# BTB_CONN.net
KiCad netlist of a schematic drawn in Altium Designer
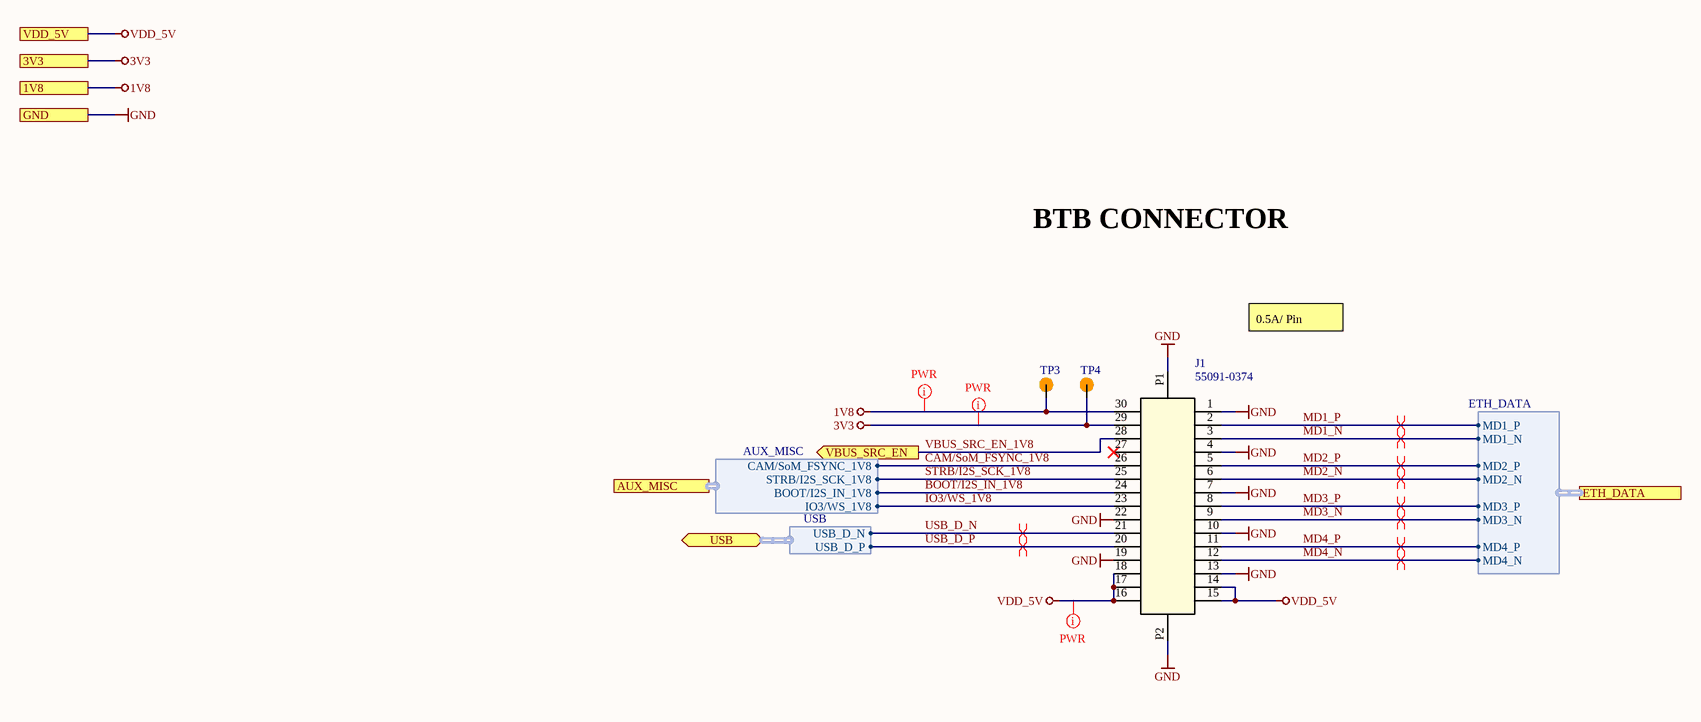
[diagram p0: BTB_CONN.SchDoc]

(export (version "E")
  (design (tool "Eeschema 10.0.6"))
  (components
    (comp (ref "J1")
      (value "55091-0374")
      (footprint "CON_550910374")
      (libsource (lib "Luxonis LLC") (part "55091-0374-Symbol-1"))
    )
    (comp (ref "TP3")
      (value "TP100_200_NS")
      (footprint "TP075_150_NS")
      (libsource (lib "Luxonis LLC") (part "TEST_POINT"))
    )
    (comp (ref "TP4")
      (value "TP100_200_NS")
      (footprint "TP075_150_NS")
      (libsource (lib "Luxonis LLC") (part "TEST_POINT"))
    )
  )
  (nets
    (net (code "4") (name "/BOOT{slash}I2S_IN_1V8") (class "Default")
      (node (ref "J1") (pin "24") (pinfunction "24_24") (pintype "passive"))
    )
    (net (code "5") (name "/CAM{slash}SoM_FSYNC_1V8") (class "Default")
      (node (ref "J1") (pin "26") (pinfunction "26_26") (pintype "passive"))
    )
    (net (code "6") (name "/IO3{slash}WS_1V8") (class "Default")
      (node (ref "J1") (pin "23") (pinfunction "23_23") (pintype "passive"))
    )
    (net (code "7") (name "/MD1_N") (class "Default")
      (node (ref "J1") (pin "3") (pinfunction "3_3") (pintype "passive"))
    )
    (net (code "8") (name "/MD1_P") (class "Default")
      (node (ref "J1") (pin "2") (pinfunction "2_2") (pintype "passive"))
    )
    (net (code "9") (name "/MD2_N") (class "Default")
      (node (ref "J1") (pin "6") (pinfunction "6_6") (pintype "passive"))
    )
    (net (code "10") (name "/MD2_P") (class "Default")
      (node (ref "J1") (pin "5") (pinfunction "5_5") (pintype "passive"))
    )
    (net (code "11") (name "/MD3_N") (class "Default")
      (node (ref "J1") (pin "9") (pinfunction "9_9") (pintype "passive"))
    )
    (net (code "12") (name "/MD3_P") (class "Default")
      (node (ref "J1") (pin "8") (pinfunction "8_8") (pintype "passive"))
    )
    (net (code "13") (name "/MD4_N") (class "Default")
      (node (ref "J1") (pin "12") (pinfunction "12_12") (pintype "passive"))
    )
    (net (code "14") (name "/MD4_P") (class "Default")
      (node (ref "J1") (pin "11") (pinfunction "11_11") (pintype "passive"))
    )
    (net (code "15") (name "/STRB{slash}I2S_SCK_1V8") (class "Default")
      (node (ref "J1") (pin "25") (pinfunction "25_25") (pintype "passive"))
    )
    (net (code "16") (name "/USB_D_N") (class "Default")
      (node (ref "J1") (pin "21") (pinfunction "21_21") (pintype "passive"))
    )
    (net (code "17") (name "/USB_D_P") (class "Default")
      (node (ref "J1") (pin "20") (pinfunction "20_20") (pintype "passive"))
    )
    (net (code "18") (name "/VBUS_SRC_EN_1V8") (class "Default")
      (node (ref "J1") (pin "28") (pinfunction "28_28") (pintype "passive"))
    )
    (net (code "22") (name "1V8") (class "Default")
      (node (ref "J1") (pin "30") (pinfunction "30_30") (pintype "passive"))
      (node (ref "TP3") (pin "1") (pintype "passive"))
    )
    (net (code "23") (name "3V3") (class "Default")
      (node (ref "J1") (pin "29") (pinfunction "29_29") (pintype "passive"))
      (node (ref "TP4") (pin "1") (pintype "passive"))
    )
    (net (code "24") (name "GND") (class "Default")
      (node (ref "J1") (pin "1") (pinfunction "1_1") (pintype "passive"))
      (node (ref "J1") (pin "10") (pinfunction "10_10") (pintype "passive"))
      (node (ref "J1") (pin "13") (pinfunction "13_13") (pintype "passive"))
      (node (ref "J1") (pin "19") (pinfunction "19_19") (pintype "passive"))
      (node (ref "J1") (pin "22") (pinfunction "22_22") (pintype "passive"))
      (node (ref "J1") (pin "4") (pinfunction "4_4") (pintype "passive"))
      (node (ref "J1") (pin "7") (pinfunction "7_7") (pintype "passive"))
      (node (ref "J1") (pin "P1") (pinfunction "P1_P1") (pintype "passive"))
      (node (ref "J1") (pin "P2") (pinfunction "P2_P2") (pintype "passive"))
    )
    (net (code "25") (name "VDD_5V") (class "Default")
      (node (ref "J1") (pin "14") (pinfunction "14_14") (pintype "passive"))
      (node (ref "J1") (pin "15") (pinfunction "15_15") (pintype "passive"))
      (node (ref "J1") (pin "16") (pinfunction "16_16") (pintype "passive"))
      (node (ref "J1") (pin "17") (pinfunction "17_17") (pintype "passive"))
      (node (ref "J1") (pin "18") (pinfunction "18_18") (pintype "passive"))
    )
    (net (code "26") (name "unconnected-(J1-Pad27)") (class "Default")
      (node (ref "J1") (pin "27") (pinfunction "27_27") (pintype "passive+no_connect"))
    )
  )
)
